# BpodFSM_2Plus_r1_2.net
KiCad netlist of a schematic drawn in EAGLE
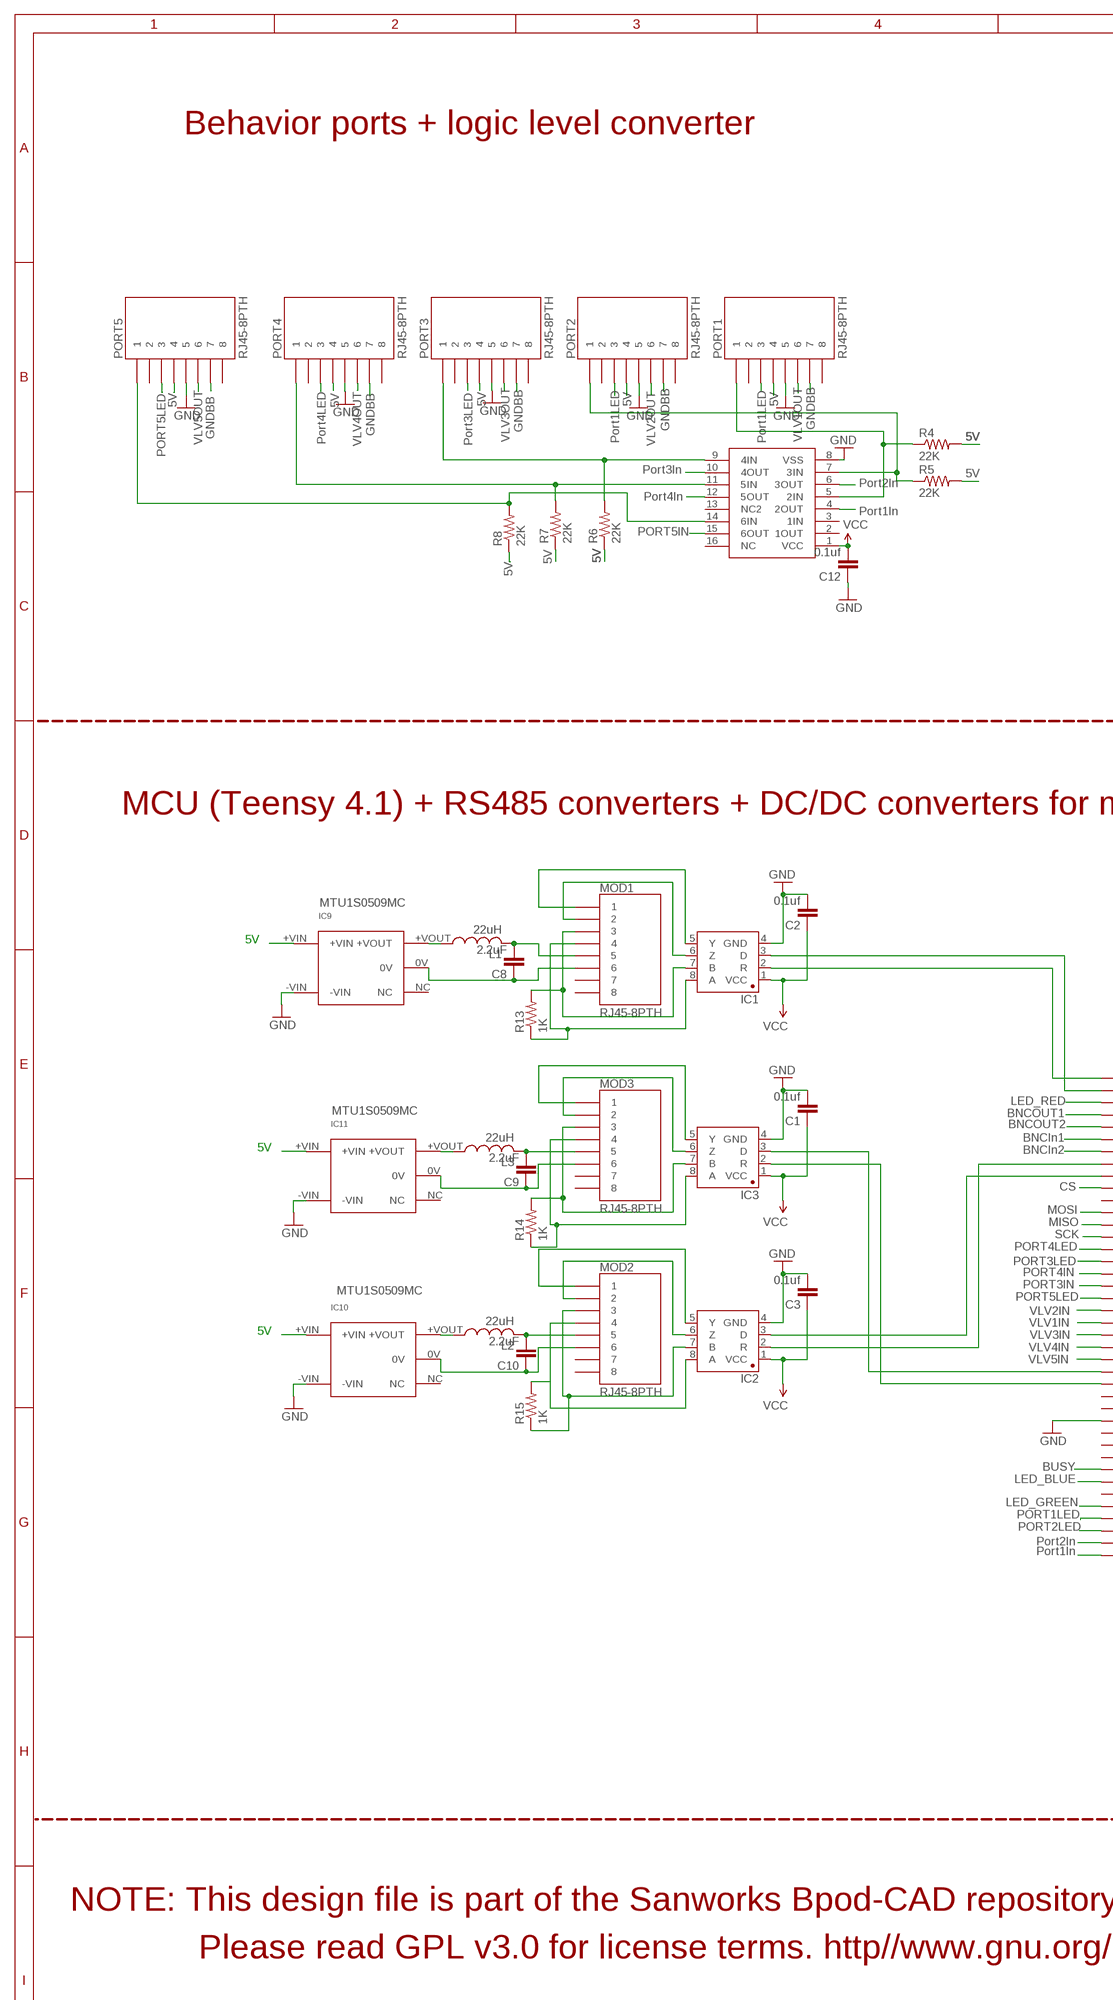
[diagram p0: schematic, sheet 1, part 1 of 2]
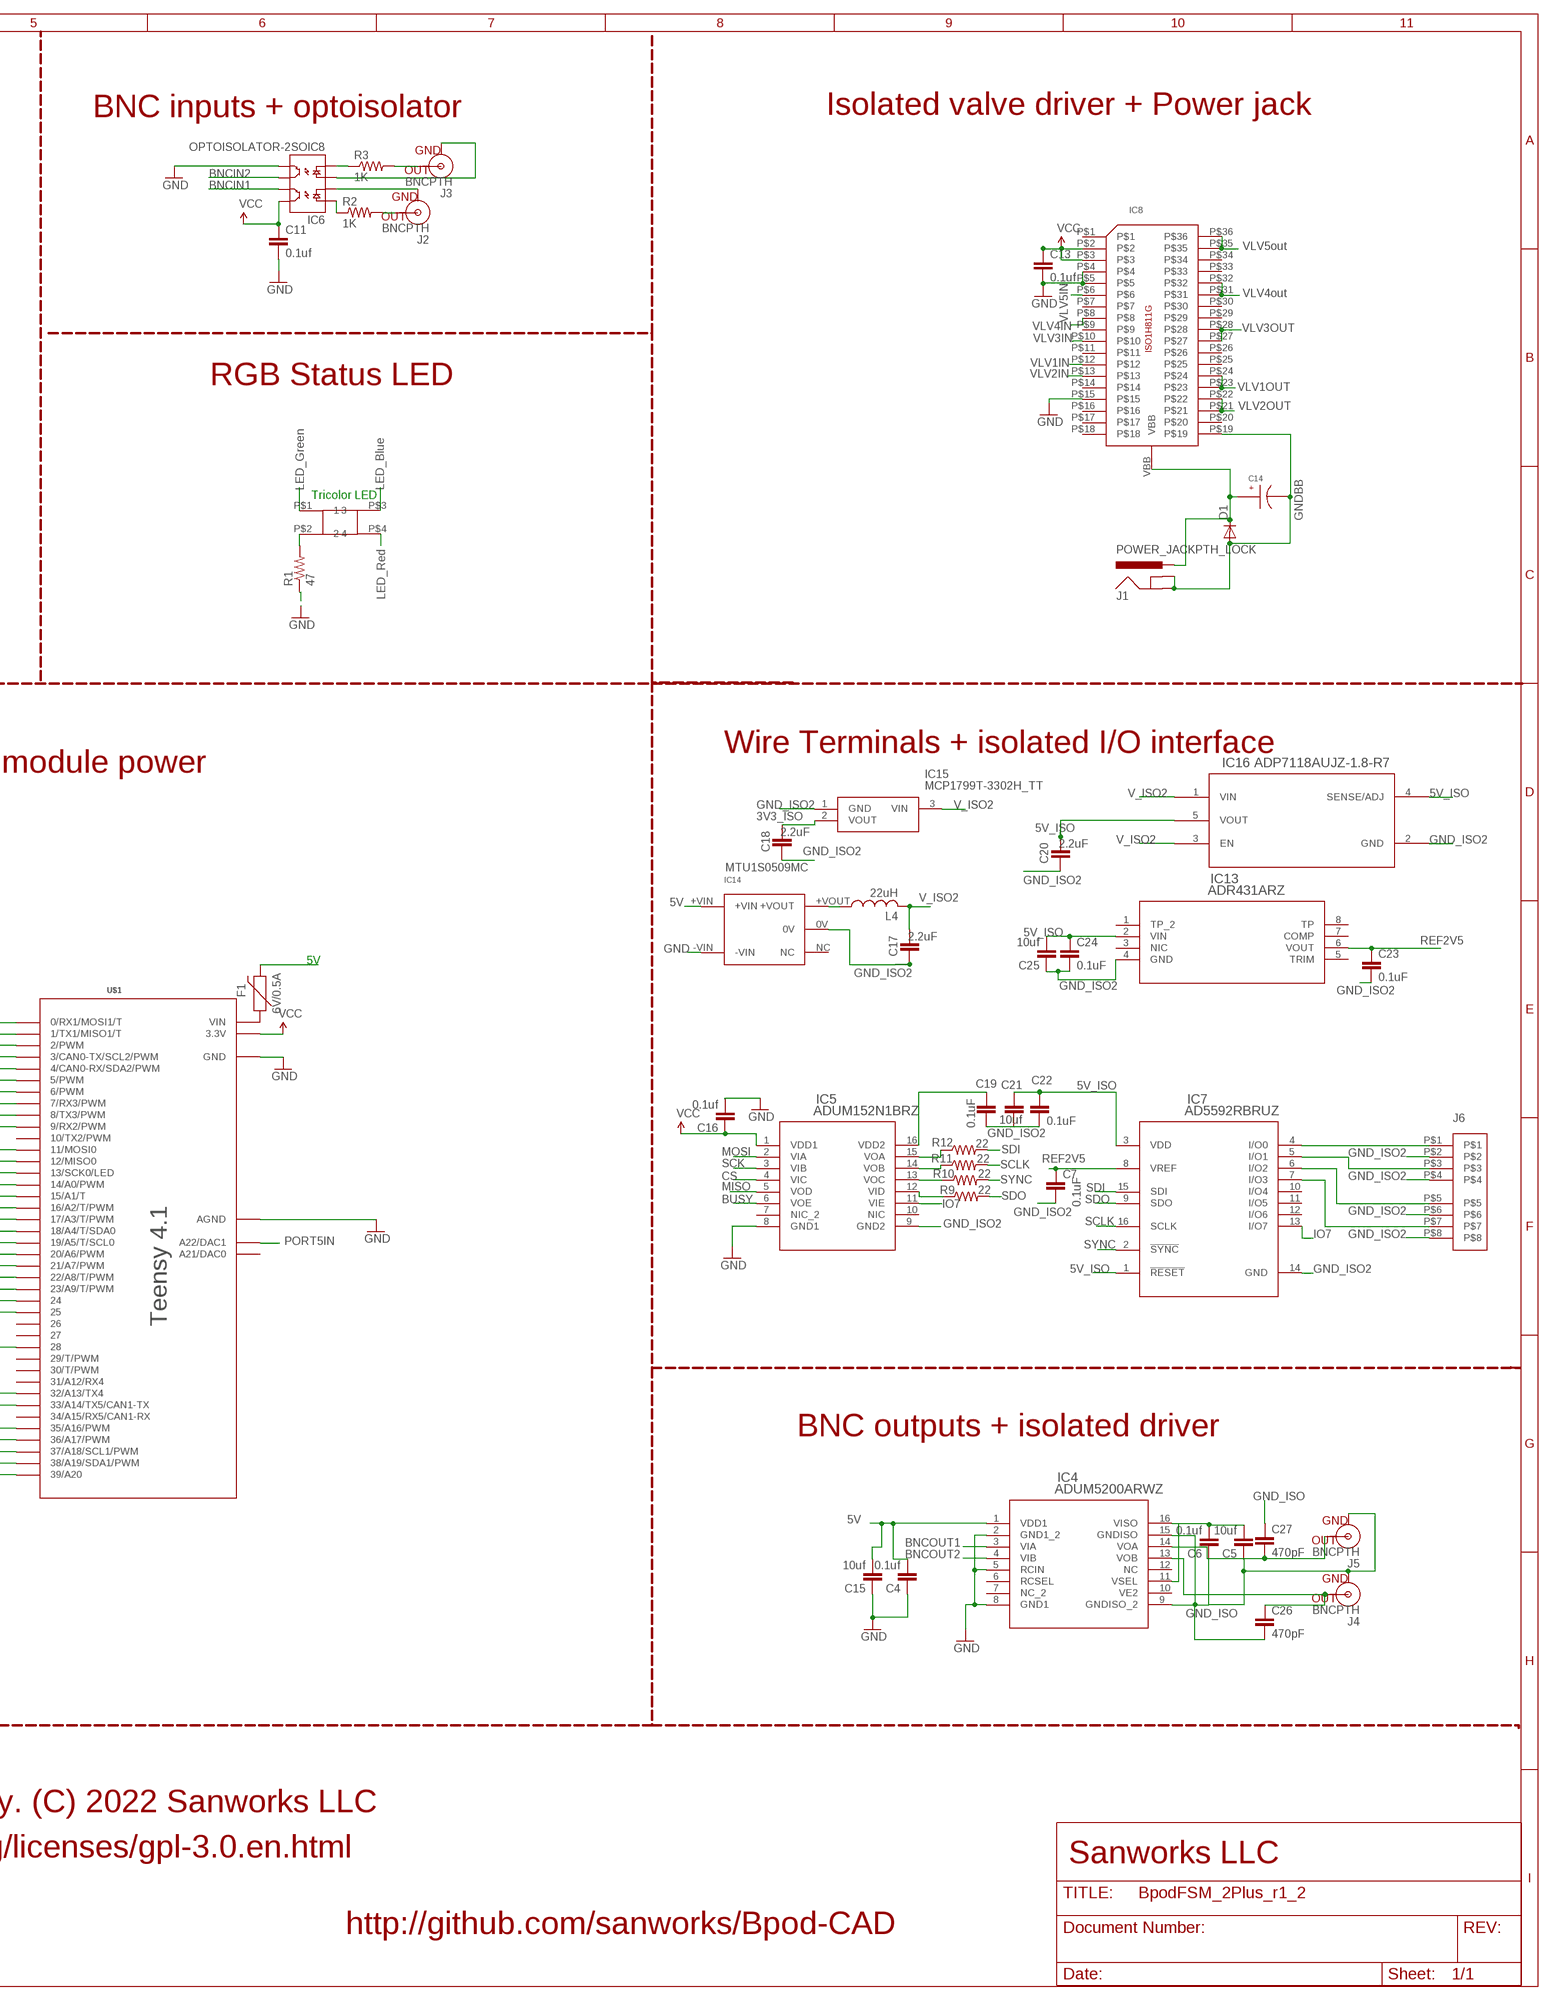
[diagram p1: schematic, sheet 1, part 2 of 2]

(export (version "E")
  (design (tool "Eeschema 10.0.6"))
  (components
    (comp (ref "C1")
      (value "0.1uf")
      (footprint "eagle-import:0805")
      (libsource (lib "eagle-import") (part "1.0UF-0805-25V-10%"))
    )
    (comp (ref "C2")
      (value "0.1uf")
      (footprint "eagle-import:0805")
      (libsource (lib "eagle-import") (part "1.0UF-0805-25V-10%"))
    )
    (comp (ref "C3")
      (value "0.1uf")
      (footprint "eagle-import:0805")
      (libsource (lib "eagle-import") (part "1.0UF-0805-25V-10%"))
    )
    (comp (ref "C4")
      (value "0.1uf")
      (footprint "eagle-import:0805")
      (libsource (lib "eagle-import") (part "1.0UF-0805-25V-10%"))
    )
    (comp (ref "C5")
      (value "10uf")
      (footprint "eagle-import:1206@1")
      (libsource (lib "eagle-import") (part "CAP1206"))
    )
    (comp (ref "C6")
      (value "0.1uf")
      (footprint "eagle-import:0805")
      (libsource (lib "eagle-import") (part "1.0UF-0805-25V-10%"))
    )
    (comp (ref "C7")
      (value "0.1uF")
      (footprint "eagle-import:0805")
      (libsource (lib "eagle-import") (part "1.0UF-0805-25V-10%"))
    )
    (comp (ref "C8")
      (value "2.2uF")
      (footprint "eagle-import:0805")
      (libsource (lib "eagle-import") (part "1.0UF-0805-25V-(+80/-20%)"))
    )
    (comp (ref "C9")
      (value "2.2uF")
      (footprint "eagle-import:0805")
      (libsource (lib "eagle-import") (part "1.0UF-0805-25V-(+80/-20%)"))
    )
    (comp (ref "C10")
      (value "2.2uF")
      (footprint "eagle-import:0805")
      (libsource (lib "eagle-import") (part "1.0UF-0805-25V-(+80/-20%)"))
    )
    (comp (ref "C11")
      (value "0.1uf")
      (footprint "eagle-import:0805")
      (libsource (lib "eagle-import") (part "1.0UF-0805-25V-10%"))
    )
    (comp (ref "C12")
      (value "0.1uf")
      (footprint "eagle-import:0805")
      (libsource (lib "eagle-import") (part "1.0UF-0805-25V-10%"))
    )
    (comp (ref "C13")
      (value "0.1uf")
      (footprint "eagle-import:0805")
      (libsource (lib "eagle-import") (part "1.0UF-0805-25V-10%"))
    )
    (comp (ref "C14")
      (value "EEE-FK1H100UR")
      (footprint "eagle-import:EEE-FK1H100UR")
      (libsource (lib "eagle-import") (part "EEE-FK1H100UR"))
    )
    (comp (ref "C15")
      (value "10uf")
      (footprint "eagle-import:1206@1")
      (libsource (lib "eagle-import") (part "CAP1206"))
    )
    (comp (ref "C16")
      (value "0.1uf")
      (footprint "eagle-import:0805")
      (libsource (lib "eagle-import") (part "1.0UF-0805-25V-10%"))
    )
    (comp (ref "C17")
      (value "2.2uF")
      (footprint "eagle-import:0805")
      (libsource (lib "eagle-import") (part "1.0UF-0805-25V-(+80/-20%)"))
    )
    (comp (ref "C18")
      (value "2.2uF")
      (footprint "eagle-import:0805")
      (libsource (lib "eagle-import") (part "1.0UF-0805-25V-(+80/-20%)"))
    )
    (comp (ref "C19")
      (value "0.1uF")
      (footprint "eagle-import:0805")
      (libsource (lib "eagle-import") (part "1.0UF-0805-25V-10%"))
    )
    (comp (ref "C20")
      (value "2.2uF")
      (footprint "eagle-import:0805")
      (libsource (lib "eagle-import") (part "1.0UF-0805-25V-(+80/-20%)"))
    )
    (comp (ref "C21")
      (value "10uf")
      (footprint "eagle-import:1206@1")
      (libsource (lib "eagle-import") (part "CAP1206"))
    )
    (comp (ref "C22")
      (value "0.1uF")
      (footprint "eagle-import:0805")
      (libsource (lib "eagle-import") (part "1.0UF-0805-25V-10%"))
    )
    (comp (ref "C23")
      (value "0.1uF")
      (footprint "eagle-import:0805")
      (libsource (lib "eagle-import") (part "1.0UF-0805-25V-10%"))
    )
    (comp (ref "C24")
      (value "0.1uF")
      (footprint "eagle-import:0805")
      (libsource (lib "eagle-import") (part "1.0UF-0805-25V-10%"))
    )
    (comp (ref "C25")
      (value "10uf")
      (footprint "eagle-import:1206@1")
      (libsource (lib "eagle-import") (part "CAP1206"))
    )
    (comp (ref "C26")
      (value "470pF")
      (footprint "eagle-import:0805")
      (libsource (lib "eagle-import") (part "1.0UF-0805-25V-10%"))
    )
    (comp (ref "C27")
      (value "470pF")
      (footprint "eagle-import:0805")
      (libsource (lib "eagle-import") (part "1.0UF-0805-25V-10%"))
    )
    (comp (ref "D1")
      (value "DIODE-DO214AA")
      (footprint "eagle-import:DO214AA")
      (libsource (lib "eagle-import") (part "DIODE-DO214AA"))
    )
    (comp (ref "F1")
      (value "6V/0.5A")
      (footprint "eagle-import:1206")
      (libsource (lib "eagle-import") (part "PPTC_HALF-AMP"))
    )
    (comp (ref "IC1")
      (value "SN65HVD31DR")
      (footprint "eagle-import:SO08")
      (libsource (lib "eagle-import") (part "SN65HVD31DR"))
    )
    (comp (ref "IC2")
      (value "SN65HVD31DR")
      (footprint "eagle-import:SO08")
      (libsource (lib "eagle-import") (part "SN65HVD31DR"))
    )
    (comp (ref "IC3")
      (value "SN65HVD31DR")
      (footprint "eagle-import:SO08")
      (libsource (lib "eagle-import") (part "SN65HVD31DR"))
    )
    (comp (ref "IC4")
      (value "ADUM5200ARWZ")
      (footprint "eagle-import:RW_16")
      (libsource (lib "eagle-import") (part "ADUM5200ARWZ"))
    )
    (comp (ref "IC5")
      (value "ADUM152N1BRZ")
      (footprint "eagle-import:R-16_ADI")
      (fields (field (name "COPYRIGHT") "Copyright (C) 2018 Accelerated Designs. All rights reserved"))
      (libsource (lib "eagle-import") (part "ADUM152N1BRZ"))
    )
    (comp (ref "IC6")
      (value "OPTOISOLATOR-2SOIC8")
      (footprint "eagle-import:SO08-2")
      (libsource (lib "eagle-import") (part "OPTOISOLATOR-2SOIC8"))
    )
    (comp (ref "IC7")
      (value "AD5592RBRUZ")
      (footprint "eagle-import:RU_16_ADI")
      (libsource (lib "eagle-import") (part "AD5592RBRUZ"))
    )
    (comp (ref "IC8")
      (value "ISO1H811G")
      (footprint "eagle-import:ISO1H811G")
      (libsource (lib "eagle-import") (part "ISO1H811G"))
    )
    (comp (ref "IC9")
      (value "9V")
      (footprint "eagle-import:MTU1D0505MC")
      (libsource (lib "eagle-import") (part "MTU1D0505MC"))
    )
    (comp (ref "IC10")
      (value "9V")
      (footprint "eagle-import:MTU1D0505MC")
      (libsource (lib "eagle-import") (part "MTU1D0505MC"))
    )
    (comp (ref "IC11")
      (value "9V")
      (footprint "eagle-import:MTU1D0505MC")
      (libsource (lib "eagle-import") (part "MTU1D0505MC"))
    )
    (comp (ref "IC12")
      (value "CD4050")
      (footprint "eagle-import:SO16")
      (libsource (lib "eagle-import") (part "CD4050"))
    )
    (comp (ref "IC13")
      (value "ADR431ARZ")
      (footprint "eagle-import:R_8_ADI")
      (libsource (lib "eagle-import") (part "ADR431ARZ"))
    )
    (comp (ref "IC14")
      (value "5V")
      (footprint "eagle-import:MTU1D0505MC")
      (libsource (lib "eagle-import") (part "MTU1D0505MC"))
    )
    (comp (ref "IC15")
      (value "MCP1799T-3302H_TT")
      (footprint "eagle-import:SOT95P237X112-3N")
      (fields
        (field (name "MANUFACTURER_PART_NUMBER") "MCP1799T-3302H/TT")
        (field (name "MOUSER_PART_NUMBER") "579-CP1799T-3302H/TT")
      )
      (libsource (lib "eagle-import") (part "MCP1799T-3302H_TT"))
    )
    (comp (ref "IC16")
      (value "ADP7118AUJZ-1.8-R7")
      (footprint "eagle-import:UJ_5")
      (libsource (lib "eagle-import") (part "ADP7118AUJZ-1.8-R7"))
    )
    (comp (ref "J1")
      (value "POWER_JACKPTH_LOCK")
      (footprint "eagle-import:POWER_JACK_PTH_LOCK")
      (libsource (lib "eagle-import") (part "POWER_JACKPTH_LOCK"))
    )
    (comp (ref "J2")
      (value "BNCPTH")
      (footprint "eagle-import:BNC")
      (libsource (lib "eagle-import") (part "BNCPTH"))
    )
    (comp (ref "J3")
      (value "BNCPTH")
      (footprint "eagle-import:BNC")
      (libsource (lib "eagle-import") (part "BNCPTH"))
    )
    (comp (ref "J4")
      (value "BNCPTH")
      (footprint "eagle-import:BNC")
      (libsource (lib "eagle-import") (part "BNCPTH"))
    )
    (comp (ref "J5")
      (value "BNCPTH")
      (footprint "eagle-import:BNC")
      (libsource (lib "eagle-import") (part "BNCPTH"))
    )
    (comp (ref "J6")
      (value "8POS_MOLEX_SOCKET")
      (footprint "eagle-import:8POS_MOLEX_SOCKET")
      (libsource (lib "eagle-import") (part "8POS_MOLEX_SOCKET"))
    )
    (comp (ref "L1")
      (value "22uH")
      (footprint "eagle-import:L3225M")
      (libsource (lib "eagle-import") (part "L-USL3225M"))
    )
    (comp (ref "L2")
      (value "22uH")
      (footprint "eagle-import:L3225M")
      (libsource (lib "eagle-import") (part "L-USL3225M"))
    )
    (comp (ref "L3")
      (value "22uH")
      (footprint "eagle-import:L3225M")
      (libsource (lib "eagle-import") (part "L-USL3225M"))
    )
    (comp (ref "L4")
      (value "22uH")
      (footprint "eagle-import:L3225M")
      (libsource (lib "eagle-import") (part "L-USL3225M"))
    )
    (comp (ref "MOD1")
      (value "RJ45-8PTH")
      (footprint "eagle-import:RJ45-8")
      (libsource (lib "eagle-import") (part "RJ45-8PTH"))
    )
    (comp (ref "MOD2")
      (value "RJ45-8PTH")
      (footprint "eagle-import:RJ45-8")
      (libsource (lib "eagle-import") (part "RJ45-8PTH"))
    )
    (comp (ref "MOD3")
      (value "RJ45-8PTH")
      (footprint "eagle-import:RJ45-8")
      (libsource (lib "eagle-import") (part "RJ45-8PTH"))
    )
    (comp (ref "PORT1")
      (value "RJ45-8PTH")
      (footprint "eagle-import:RJ45-8")
      (libsource (lib "eagle-import") (part "RJ45-8PTH"))
    )
    (comp (ref "PORT2")
      (value "RJ45-8PTH")
      (footprint "eagle-import:RJ45-8")
      (libsource (lib "eagle-import") (part "RJ45-8PTH"))
    )
    (comp (ref "PORT3")
      (value "RJ45-8PTH")
      (footprint "eagle-import:RJ45-8")
      (libsource (lib "eagle-import") (part "RJ45-8PTH"))
    )
    (comp (ref "PORT4")
      (value "RJ45-8PTH")
      (footprint "eagle-import:RJ45-8")
      (libsource (lib "eagle-import") (part "RJ45-8PTH"))
    )
    (comp (ref "PORT5")
      (value "RJ45-8PTH")
      (footprint "eagle-import:RJ45-8")
      (libsource (lib "eagle-import") (part "RJ45-8PTH"))
    )
    (comp (ref "R1")
      (value "47")
      (footprint "eagle-import:1206")
      (libsource (lib "eagle-import") (part "RESISTOR1206"))
    )
    (comp (ref "R2")
      (value "1K")
      (footprint "eagle-import:1206")
      (libsource (lib "eagle-import") (part "SparkFun-Resistors_RESISTOR1206"))
    )
    (comp (ref "R3")
      (value "1K")
      (footprint "eagle-import:1206")
      (libsource (lib "eagle-import") (part "SparkFun-Resistors_RESISTOR1206"))
    )
    (comp (ref "R4")
      (value "22K")
      (footprint "eagle-import:1206")
      (libsource (lib "eagle-import") (part "SparkFun-Resistors_RESISTOR1206"))
    )
    (comp (ref "R5")
      (value "22K")
      (footprint "eagle-import:1206")
      (libsource (lib "eagle-import") (part "SparkFun-Resistors_RESISTOR1206"))
    )
    (comp (ref "R6")
      (value "22K")
      (footprint "eagle-import:1206")
      (libsource (lib "eagle-import") (part "SparkFun-Resistors_RESISTOR1206"))
    )
    (comp (ref "R7")
      (value "22K")
      (footprint "eagle-import:1206")
      (libsource (lib "eagle-import") (part "SparkFun-Resistors_RESISTOR1206"))
    )
    (comp (ref "R8")
      (value "22K")
      (footprint "eagle-import:1206")
      (libsource (lib "eagle-import") (part "SparkFun-Resistors_RESISTOR1206"))
    )
    (comp (ref "R9")
      (value "22")
      (footprint "eagle-import:R0805")
      (libsource (lib "eagle-import") (part "R-US_R0805"))
    )
    (comp (ref "R10")
      (value "22")
      (footprint "eagle-import:R0805")
      (libsource (lib "eagle-import") (part "R-US_R0805"))
    )
    (comp (ref "R11")
      (value "22")
      (footprint "eagle-import:R0805")
      (libsource (lib "eagle-import") (part "R-US_R0805"))
    )
    (comp (ref "R12")
      (value "22")
      (footprint "eagle-import:R0805")
      (libsource (lib "eagle-import") (part "R-US_R0805"))
    )
    (comp (ref "R13")
      (value "1K")
      (footprint "eagle-import:1206")
      (libsource (lib "eagle-import") (part "SparkFun-Resistors_RESISTOR1206"))
    )
    (comp (ref "R14")
      (value "1K")
      (footprint "eagle-import:1206")
      (libsource (lib "eagle-import") (part "SparkFun-Resistors_RESISTOR1206"))
    )
    (comp (ref "R15")
      (value "1K")
      (footprint "eagle-import:1206")
      (libsource (lib "eagle-import") (part "SparkFun-Resistors_RESISTOR1206"))
    )
    (comp (ref "U$1")
      (value "TEENSY_3.6_DIL")
      (footprint "eagle-import:TEENSY_3.6_DIL")
      (libsource (lib "eagle-import") (part "TEENSY_3.6_DIL"))
    )
    (comp (ref "U$8")
      (value "SQUARE_TRICOLOR_LED")
      (footprint "eagle-import:SQUARE_TRICOLOR_LED")
      (libsource (lib "eagle-import") (part "SQUARE_TRICOLOR_LED"))
    )
  )
  (nets
    (net (code "1") (name "/3V3_ISO") (class "Default")
      (node (ref "C18") (pin "2") (pinfunction "2_2") (pintype "passive"))
      (node (ref "C19") (pin "1") (pinfunction "1_1") (pintype "passive"))
      (node (ref "IC15") (pin "2") (pinfunction "VOUT_2") (pintype "bidirectional"))
      (node (ref "IC5") (pin "16") (pinfunction "VDD2_16") (pintype "power_in"))
    )
    (net (code "2") (name "/5V") (class "Default")
      (node (ref "C15") (pin "2") (pinfunction "2_2") (pintype "passive"))
      (node (ref "C4") (pin "2") (pinfunction "2_2") (pintype "passive"))
      (node (ref "F1") (pin "2") (pinfunction "2_2") (pintype "bidirectional"))
      (node (ref "IC10") (pin "+VIN") (pinfunction "+VIN_+VIN") (pintype "bidirectional"))
      (node (ref "IC11") (pin "+VIN") (pinfunction "+VIN_+VIN") (pintype "bidirectional"))
      (node (ref "IC14") (pin "+VIN") (pinfunction "+VIN_+VIN") (pintype "bidirectional"))
      (node (ref "IC4") (pin "1") (pinfunction "VDD1_1") (pintype "passive"))
      (node (ref "IC9") (pin "+VIN") (pinfunction "+VIN_+VIN") (pintype "bidirectional"))
      (node (ref "PORT1") (pin "4") (pinfunction "4_4") (pintype "bidirectional"))
      (node (ref "PORT2") (pin "4") (pinfunction "4_4") (pintype "bidirectional"))
      (node (ref "PORT3") (pin "4") (pinfunction "4_4") (pintype "bidirectional"))
      (node (ref "PORT4") (pin "4") (pinfunction "4_4") (pintype "bidirectional"))
      (node (ref "PORT5") (pin "4") (pinfunction "4_4") (pintype "bidirectional"))
      (node (ref "R4") (pin "2") (pinfunction "2_2") (pintype "passive"))
      (node (ref "R5") (pin "2") (pinfunction "2_2") (pintype "passive"))
      (node (ref "R6") (pin "1") (pinfunction "1_1") (pintype "passive"))
      (node (ref "R7") (pin "1") (pinfunction "1_1") (pintype "passive"))
      (node (ref "R8") (pin "1") (pinfunction "1_1") (pintype "passive"))
    )
    (net (code "3") (name "/5V_ISO") (class "Default")
      (node (ref "C20") (pin "2") (pinfunction "2_2") (pintype "passive"))
      (node (ref "C21") (pin "2") (pinfunction "2_2") (pintype "passive"))
      (node (ref "C22") (pin "1") (pinfunction "1_1") (pintype "passive"))
      (node (ref "C24") (pin "1") (pinfunction "1_1") (pintype "passive"))
      (node (ref "C25") (pin "2") (pinfunction "2_2") (pintype "passive"))
      (node (ref "IC13") (pin "2") (pinfunction "VIN_2") (pintype "input"))
      (node (ref "IC16") (pin "4") (pinfunction "SENSE/ADJ_4") (pintype "passive"))
      (node (ref "IC16") (pin "5") (pinfunction "VOUT_5") (pintype "passive"))
      (node (ref "IC7") (pin "1") (pinfunction "~{RESET}_1") (pintype "passive"))
      (node (ref "IC7") (pin "3") (pinfunction "VDD_3") (pintype "passive"))
    )
    (net (code "4") (name "/BNCIN1") (class "Default")
      (node (ref "IC6") (pin "7") (pinfunction "EM1_7") (pintype "bidirectional"))
      (node (ref "U$1") (pin "6") (pinfunction "6/PWM_6") (pintype "bidirectional"))
    )
    (net (code "5") (name "/BNCIN2") (class "Default")
      (node (ref "IC6") (pin "6") (pinfunction "CL2_6") (pintype "bidirectional"))
      (node (ref "U$1") (pin "5") (pinfunction "5/PWM_5") (pintype "bidirectional"))
    )
    (net (code "6") (name "/BNCOUT1") (class "Default")
      (node (ref "IC4") (pin "3") (pinfunction "VIA_3") (pintype "passive"))
      (node (ref "U$1") (pin "3") (pinfunction "3/CAN0-TX/SCL2/PWM_3") (pintype "bidirectional"))
    )
    (net (code "7") (name "/BNCOUT2") (class "Default")
      (node (ref "IC4") (pin "4") (pinfunction "VIB_4") (pintype "passive"))
      (node (ref "U$1") (pin "4") (pinfunction "4/CAN0-RX/SDA2/PWM_4") (pintype "bidirectional"))
    )
    (net (code "8") (name "/BUSY") (class "Default")
      (node (ref "IC5") (pin "6") (pinfunction "VOE_6") (pintype "output"))
      (node (ref "U$1") (pin "32/A13") (pinfunction "32/A13/TX4_32/A13") (pintype "bidirectional"))
    )
    (net (code "9") (name "/CS") (class "Default")
      (node (ref "IC5") (pin "4") (pinfunction "VIC_4") (pintype "input"))
      (node (ref "U$1") (pin "9") (pinfunction "9/RX2/PWM_9") (pintype "bidirectional"))
    )
    (net (code "10") (name "/GNDBB") (class "Default")
      (node (ref "C14") (pin "CATHODE") (pinfunction "CATHODE_CATHODE") (pintype "bidirectional"))
      (node (ref "D1") (pin "A") (pinfunction "A_A") (pintype "passive"))
      (node (ref "IC8") (pin "P$19") (pinfunction "P$19_P$19") (pintype "bidirectional"))
      (node (ref "J1") (pin "GND") (pinfunction "GND_GND") (pintype "bidirectional"))
      (node (ref "J1") (pin "GNDBREAK") (pinfunction "GNDBREAK_GNDBREAK") (pintype "bidirectional"))
      (node (ref "PORT1") (pin "7") (pinfunction "7_7") (pintype "bidirectional"))
      (node (ref "PORT2") (pin "7") (pinfunction "7_7") (pintype "bidirectional"))
      (node (ref "PORT3") (pin "7") (pinfunction "7_7") (pintype "bidirectional"))
      (node (ref "PORT4") (pin "7") (pinfunction "7_7") (pintype "bidirectional"))
      (node (ref "PORT5") (pin "7") (pinfunction "7_7") (pintype "bidirectional"))
    )
    (net (code "11") (name "/GND_ISO") (class "Default")
      (node (ref "C26") (pin "2") (pinfunction "2_2") (pintype "passive"))
      (node (ref "C27") (pin "1") (pinfunction "1_1") (pintype "passive"))
      (node (ref "C5") (pin "1") (pinfunction "1_1") (pintype "passive"))
      (node (ref "C6") (pin "1") (pinfunction "1_1") (pintype "passive"))
      (node (ref "IC4") (pin "15") (pinfunction "GNDISO_15") (pintype "passive"))
      (node (ref "IC4") (pin "9") (pinfunction "GNDISO_2_9") (pintype "passive"))
      (node (ref "J4") (pin "GND") (pinfunction "GND_GND") (pintype "bidirectional"))
      (node (ref "J5") (pin "GND") (pinfunction "GND_GND") (pintype "bidirectional"))
    )
    (net (code "12") (name "/GND_ISO2") (class "Default")
      (node (ref "C17") (pin "1") (pinfunction "1_1") (pintype "passive"))
      (node (ref "C18") (pin "1") (pinfunction "1_1") (pintype "passive"))
      (node (ref "C19") (pin "2") (pinfunction "2_2") (pintype "passive"))
      (node (ref "C20") (pin "1") (pinfunction "1_1") (pintype "passive"))
      (node (ref "C21") (pin "1") (pinfunction "1_1") (pintype "passive"))
      (node (ref "C22") (pin "2") (pinfunction "2_2") (pintype "passive"))
      (node (ref "C23") (pin "2") (pinfunction "2_2") (pintype "passive"))
      (node (ref "C24") (pin "2") (pinfunction "2_2") (pintype "passive"))
      (node (ref "C25") (pin "1") (pinfunction "1_1") (pintype "passive"))
      (node (ref "C7") (pin "2") (pinfunction "2_2") (pintype "passive"))
      (node (ref "IC13") (pin "4") (pinfunction "GND_4") (pintype "power_in"))
      (node (ref "IC14") (pin "0V") (pinfunction "0V_0V") (pintype "bidirectional"))
      (node (ref "IC15") (pin "1") (pinfunction "GND_1") (pintype "bidirectional"))
      (node (ref "IC16") (pin "2") (pinfunction "GND_2") (pintype "passive"))
      (node (ref "IC5") (pin "9") (pinfunction "GND2_9") (pintype "passive"))
      (node (ref "IC7") (pin "14") (pinfunction "GND_14") (pintype "passive"))
      (node (ref "J6") (pin "P$2") (pinfunction "P$2_P$2") (pintype "bidirectional"))
      (node (ref "J6") (pin "P$4") (pinfunction "P$4_P$4") (pintype "bidirectional"))
      (node (ref "J6") (pin "P$6") (pinfunction "P$6_P$6") (pintype "bidirectional"))
      (node (ref "J6") (pin "P$8") (pinfunction "P$8_P$8") (pintype "bidirectional"))
    )
    (net (code "13") (name "/IO7") (class "Default")
      (node (ref "IC5") (pin "11") (pinfunction "VIE_11") (pintype "input"))
      (node (ref "IC7") (pin "13") (pinfunction "I/O7_13") (pintype "passive"))
    )
    (net (code "14") (name "/LED_BLUE") (class "Default")
      (node (ref "U$1") (pin "33/A14") (pinfunction "33/A14/TX5/CAN1-TX_33/A14") (pintype "bidirectional"))
      (node (ref "U$8") (pin "P$3") (pinfunction "3_P$3") (pintype "bidirectional"))
    )
    (net (code "15") (name "/LED_GREEN") (class "Default")
      (node (ref "U$1") (pin "35/A16") (pinfunction "35/A16/PWM_35/A16") (pintype "bidirectional"))
      (node (ref "U$8") (pin "P$1") (pinfunction "1_P$1") (pintype "bidirectional"))
    )
    (net (code "16") (name "/LED_RED") (class "Default")
      (node (ref "U$1") (pin "2") (pinfunction "2/PWM_2") (pintype "bidirectional"))
      (node (ref "U$8") (pin "P$4") (pinfunction "4_P$4") (pintype "bidirectional"))
    )
    (net (code "17") (name "/MISO") (class "Default")
      (node (ref "IC5") (pin "5") (pinfunction "VOD_5") (pintype "output"))
      (node (ref "U$1") (pin "12") (pinfunction "12/MISO0_12") (pintype "bidirectional"))
    )
    (net (code "18") (name "/MOSI") (class "Default")
      (node (ref "IC5") (pin "2") (pinfunction "VIA_2") (pintype "input"))
      (node (ref "U$1") (pin "11") (pinfunction "11/MOSI0_11") (pintype "bidirectional"))
    )
    (net (code "19") (name "/PORT1IN") (class "Default")
      (node (ref "IC12") (pin "4") (pinfunction "2OUT_4") (pintype "bidirectional"))
      (node (ref "U$1") (pin "39/A20") (pinfunction "39/A20_39/A20") (pintype "bidirectional"))
    )
    (net (code "20") (name "/PORT1LED") (class "Default")
      (node (ref "PORT1") (pin "3") (pinfunction "3_3") (pintype "bidirectional"))
      (node (ref "U$1") (pin "36/A17") (pinfunction "36/A17/PWM_36/A17") (pintype "bidirectional"))
    )
    (net (code "21") (name "/PORT2IN") (class "Default")
      (node (ref "IC12") (pin "6") (pinfunction "3OUT_6") (pintype "bidirectional"))
      (node (ref "U$1") (pin "38/A19") (pinfunction "38/A19/SDA1/PWM_38/A19") (pintype "bidirectional"))
    )
    (net (code "22") (name "/PORT2LED") (class "Default")
      (node (ref "PORT2") (pin "3") (pinfunction "3_3") (pintype "bidirectional"))
      (node (ref "U$1") (pin "37/A18") (pinfunction "37/A18/SCL1/PWM_37/A18") (pintype "bidirectional"))
    )
    (net (code "23") (name "/PORT3IN") (class "Default")
      (node (ref "IC12") (pin "10") (pinfunction "4OUT_10") (pintype "bidirectional"))
      (node (ref "U$1") (pin "17/A3") (pinfunction "17/A3/T/PWM_17/A3") (pintype "bidirectional"))
    )
    (net (code "24") (name "/PORT3LED") (class "Default")
      (node (ref "PORT3") (pin "3") (pinfunction "3_3") (pintype "bidirectional"))
      (node (ref "U$1") (pin "15/A1") (pinfunction "15/A1/T_15/A1") (pintype "bidirectional"))
    )
    (net (code "25") (name "/PORT4IN") (class "Default")
      (node (ref "IC12") (pin "12") (pinfunction "5OUT_12") (pintype "bidirectional"))
      (node (ref "U$1") (pin "16/A2") (pinfunction "16/A2/T/PWM_16/A2") (pintype "bidirectional"))
    )
    (net (code "26") (name "/PORT4LED") (class "Default")
      (node (ref "PORT4") (pin "3") (pinfunction "3_3") (pintype "bidirectional"))
      (node (ref "U$1") (pin "14/A0") (pinfunction "14/A0/PWM_14/A0") (pintype "bidirectional"))
    )
    (net (code "27") (name "/PORT5IN") (class "Default")
      (node (ref "IC12") (pin "15") (pinfunction "6OUT_15") (pintype "bidirectional"))
      (node (ref "U$1") (pin "A22") (pinfunction "A22/DAC1_A22") (pintype "bidirectional"))
    )
    (net (code "28") (name "/PORT5LED") (class "Default")
      (node (ref "PORT5") (pin "3") (pinfunction "3_3") (pintype "bidirectional"))
      (node (ref "U$1") (pin "18/A4") (pinfunction "18/A4/T/SDA0_18/A4") (pintype "bidirectional"))
    )
    (net (code "29") (name "/REF2V5") (class "Default")
      (node (ref "C23") (pin "1") (pinfunction "1_1") (pintype "passive"))
      (node (ref "C7") (pin "1") (pinfunction "1_1") (pintype "passive"))
      (node (ref "IC13") (pin "6") (pinfunction "VOUT_6") (pintype "output"))
      (node (ref "IC7") (pin "8") (pinfunction "VREF_8") (pintype "passive"))
    )
    (net (code "30") (name "/SCK") (class "Default")
      (node (ref "IC5") (pin "3") (pinfunction "VIB_3") (pintype "input"))
      (node (ref "U$1") (pin "13") (pinfunction "13/SCK0/LED_13") (pintype "bidirectional"))
    )
    (net (code "31") (name "/SCLK") (class "Default")
      (node (ref "IC7") (pin "16") (pinfunction "SCLK_16") (pintype "passive"))
      (node (ref "R11") (pin "2") (pinfunction "2_2") (pintype "passive"))
    )
    (net (code "32") (name "/SDI") (class "Default")
      (node (ref "IC7") (pin "15") (pinfunction "SDI_15") (pintype "passive"))
      (node (ref "R12") (pin "2") (pinfunction "2_2") (pintype "passive"))
    )
    (net (code "33") (name "/SDO") (class "Default")
      (node (ref "IC7") (pin "9") (pinfunction "SDO_9") (pintype "passive"))
      (node (ref "R9") (pin "2") (pinfunction "2_2") (pintype "passive"))
    )
    (net (code "34") (name "/SYNC") (class "Default")
      (node (ref "IC7") (pin "2") (pinfunction "~{SYNC}_2") (pintype "passive"))
      (node (ref "R10") (pin "2") (pinfunction "2_2") (pintype "passive"))
    )
    (net (code "35") (name "/VLV1IN") (class "Default")
      (node (ref "IC8") (pin "P$12") (pinfunction "P$12_P$12") (pintype "bidirectional"))
      (node (ref "U$1") (pin "20/A6") (pinfunction "20/A6/PWM_20/A6") (pintype "bidirectional"))
    )
    (net (code "36") (name "/VLV1OUT") (class "Default")
      (node (ref "IC8") (pin "P$23") (pinfunction "P$23_P$23") (pintype "bidirectional"))
      (node (ref "IC8") (pin "P$24") (pinfunction "P$24_P$24") (pintype "bidirectional"))
      (node (ref "PORT1") (pin "6") (pinfunction "6_6") (pintype "bidirectional"))
    )
    (net (code "37") (name "/VLV2IN") (class "Default")
      (node (ref "IC8") (pin "P$13") (pinfunction "P$13_P$13") (pintype "bidirectional"))
      (node (ref "U$1") (pin "19/A5") (pinfunction "19/A5/T/SCL0_19/A5") (pintype "bidirectional"))
    )
    (net (code "38") (name "/VLV2OUT") (class "Default")
      (node (ref "IC8") (pin "P$21") (pinfunction "P$21_P$21") (pintype "bidirectional"))
      (node (ref "IC8") (pin "P$22") (pinfunction "P$22_P$22") (pintype "bidirectional"))
      (node (ref "PORT2") (pin "6") (pinfunction "6_6") (pintype "bidirectional"))
    )
    (net (code "39") (name "/VLV3IN") (class "Default")
      (node (ref "IC8") (pin "P$10") (pinfunction "P$10_P$10") (pintype "bidirectional"))
      (node (ref "U$1") (pin "21/A7") (pinfunction "21/A7/PWM_21/A7") (pintype "bidirectional"))
    )
    (net (code "40") (name "/VLV3OUT") (class "Default")
      (node (ref "IC8") (pin "P$27") (pinfunction "P$27_P$27") (pintype "bidirectional"))
      (node (ref "IC8") (pin "P$28") (pinfunction "P$28_P$28") (pintype "bidirectional"))
      (node (ref "PORT3") (pin "6") (pinfunction "6_6") (pintype "bidirectional"))
    )
    (net (code "41") (name "/VLV4IN") (class "Default")
      (node (ref "IC8") (pin "P$8") (pinfunction "P$8_P$8") (pintype "bidirectional"))
      (node (ref "U$1") (pin "22/A8") (pinfunction "22/A8/T/PWM_22/A8") (pintype "bidirectional"))
    )
    (net (code "42") (name "/VLV4OUT") (class "Default")
      (node (ref "IC8") (pin "P$31") (pinfunction "P$31_P$31") (pintype "bidirectional"))
      (node (ref "IC8") (pin "P$32") (pinfunction "P$32_P$32") (pintype "bidirectional"))
      (node (ref "PORT4") (pin "6") (pinfunction "6_6") (pintype "bidirectional"))
    )
    (net (code "43") (name "/VLV5IN") (class "Default")
      (node (ref "IC8") (pin "P$6") (pinfunction "P$6_P$6") (pintype "bidirectional"))
      (node (ref "U$1") (pin "23/A9") (pinfunction "23/A9/T/PWM_23/A9") (pintype "bidirectional"))
    )
    (net (code "44") (name "/VLV5OUT") (class "Default")
      (node (ref "IC8") (pin "P$35") (pinfunction "P$35_P$35") (pintype "bidirectional"))
      (node (ref "IC8") (pin "P$36") (pinfunction "P$36_P$36") (pintype "bidirectional"))
      (node (ref "PORT5") (pin "6") (pinfunction "6_6") (pintype "bidirectional"))
    )
    (net (code "45") (name "/V_ISO2") (class "Default")
      (node (ref "C17") (pin "2") (pinfunction "2_2") (pintype "passive"))
      (node (ref "IC15") (pin "3") (pinfunction "VIN_3") (pintype "bidirectional"))
      (node (ref "IC16") (pin "1") (pinfunction "VIN_1") (pintype "passive"))
      (node (ref "IC16") (pin "3") (pinfunction "EN_3") (pintype "passive"))
      (node (ref "L4") (pin "2") (pinfunction "2_2") (pintype "passive"))
    )
    (net (code "46") (name "GND") (class "Default")
      (node (ref "C1") (pin "2") (pinfunction "2_2") (pintype "passive"))
      (node (ref "C11") (pin "2") (pinfunction "2_2") (pintype "passive"))
      (node (ref "C12") (pin "1") (pinfunction "1_1") (pintype "passive"))
      (node (ref "C13") (pin "2") (pinfunction "2_2") (pintype "passive"))
      (node (ref "C15") (pin "1") (pinfunction "1_1") (pintype "passive"))
      (node (ref "C16") (pin "2") (pinfunction "2_2") (pintype "passive"))
      (node (ref "C2") (pin "2") (pinfunction "2_2") (pintype "passive"))
      (node (ref "C3") (pin "2") (pinfunction "2_2") (pintype "passive"))
      (node (ref "C4") (pin "1") (pinfunction "1_1") (pintype "passive"))
      (node (ref "IC1") (pin "4") (pinfunction "GND_4") (pintype "bidirectional"))
      (node (ref "IC10") (pin "-VIN") (pinfunction "-VIN_-VIN") (pintype "bidirectional"))
      (node (ref "IC11") (pin "-VIN") (pinfunction "-VIN_-VIN") (pintype "bidirectional"))
      (node (ref "IC12") (pin "8") (pinfunction "VSS_8") (pintype "bidirectional"))
      (node (ref "IC14") (pin "-VIN") (pinfunction "-VIN_-VIN") (pintype "bidirectional"))
      (node (ref "IC2") (pin "4") (pinfunction "GND_4") (pintype "bidirectional"))
      (node (ref "IC3") (pin "4") (pinfunction "GND_4") (pintype "bidirectional"))
      (node (ref "IC4") (pin "2") (pinfunction "GND1_2_2") (pintype "passive"))
      (node (ref "IC4") (pin "5") (pinfunction "RCIN_5") (pintype "passive"))
      (node (ref "IC4") (pin "8") (pinfunction "GND1_8") (pintype "passive"))
      (node (ref "IC5") (pin "8") (pinfunction "GND1_8") (pintype "passive"))
      (node (ref "IC6") (pin "5") (pinfunction "EM2_5") (pintype "bidirectional"))
      (node (ref "IC8") (pin "P$15") (pinfunction "P$15_P$15") (pintype "bidirectional"))
      (node (ref "IC8") (pin "P$4") (pinfunction "P$4_P$4") (pintype "bidirectional"))
      (node (ref "IC8") (pin "P$5") (pinfunction "P$5_P$5") (pintype "bidirectional"))
      (node (ref "IC9") (pin "-VIN") (pinfunction "-VIN_-VIN") (pintype "bidirectional"))
      (node (ref "PORT1") (pin "5") (pinfunction "5_5") (pintype "bidirectional"))
      (node (ref "PORT2") (pin "5") (pinfunction "5_5") (pintype "bidirectional"))
      (node (ref "PORT3") (pin "5") (pinfunction "5_5") (pintype "bidirectional"))
      (node (ref "PORT4") (pin "5") (pinfunction "5_5") (pintype "bidirectional"))
      (node (ref "PORT5") (pin "5") (pinfunction "5_5") (pintype "bidirectional"))
      (node (ref "R1") (pin "1") (pinfunction "1_1") (pintype "passive"))
      (node (ref "U$1") (pin "28") (pinfunction "28_28") (pintype "bidirectional"))
      (node (ref "U$1") (pin "AGND") (pinfunction "AGND_AGND") (pintype "power_in"))
      (node (ref "U$1") (pin "GND") (pinfunction "GND_GND") (pintype "power_in"))
      (node (ref "U$1") (pin "GND1") (pinfunction "GND_GND1") (pintype "power_in"))
    )
    (net (code "47") (name "Net-(C8-Pad1)") (class "Default")
      (node (ref "C8") (pin "1") (pinfunction "1_1") (pintype "passive"))
      (node (ref "IC9") (pin "0V") (pinfunction "0V_0V") (pintype "bidirectional"))
      (node (ref "MOD1") (pin "6") (pinfunction "6_6") (pintype "bidirectional"))
    )
    (net (code "48") (name "Net-(C8-Pad2)") (class "Default")
      (node (ref "C8") (pin "2") (pinfunction "2_2") (pintype "passive"))
      (node (ref "L1") (pin "2") (pinfunction "2_2") (pintype "passive"))
      (node (ref "MOD1") (pin "5") (pinfunction "5_5") (pintype "bidirectional"))
    )
    (net (code "49") (name "Net-(C9-Pad1)") (class "Default")
      (node (ref "C9") (pin "1") (pinfunction "1_1") (pintype "passive"))
      (node (ref "IC11") (pin "0V") (pinfunction "0V_0V") (pintype "bidirectional"))
      (node (ref "MOD3") (pin "6") (pinfunction "6_6") (pintype "bidirectional"))
    )
    (net (code "50") (name "Net-(C9-Pad2)") (class "Default")
      (node (ref "C9") (pin "2") (pinfunction "2_2") (pintype "passive"))
      (node (ref "L3") (pin "2") (pinfunction "2_2") (pintype "passive"))
      (node (ref "MOD3") (pin "5") (pinfunction "5_5") (pintype "bidirectional"))
    )
    (net (code "51") (name "Net-(C10-Pad1)") (class "Default")
      (node (ref "C10") (pin "1") (pinfunction "1_1") (pintype "passive"))
      (node (ref "IC10") (pin "0V") (pinfunction "0V_0V") (pintype "bidirectional"))
      (node (ref "MOD2") (pin "6") (pinfunction "6_6") (pintype "bidirectional"))
    )
    (net (code "52") (name "Net-(C10-Pad2)") (class "Default")
      (node (ref "C10") (pin "2") (pinfunction "2_2") (pintype "passive"))
      (node (ref "L2") (pin "2") (pinfunction "2_2") (pintype "passive"))
      (node (ref "MOD2") (pin "5") (pinfunction "5_5") (pintype "bidirectional"))
    )
    (net (code "53") (name "Net-(C14-PadANODE)") (class "Default")
      (node (ref "C14") (pin "ANODE") (pinfunction "ANODE_ANODE") (pintype "bidirectional"))
      (node (ref "D1") (pin "C") (pinfunction "C_C") (pintype "passive"))
      (node (ref "IC8") (pin "VBB") (pinfunction "VBB_VBB") (pintype "bidirectional"))
      (node (ref "J1") (pin "PWR") (pinfunction "PWR_PWR") (pintype "bidirectional"))
    )
    (net (code "54") (name "Net-(F1-Pad1)") (class "Default")
      (node (ref "F1") (pin "1") (pinfunction "1_1") (pintype "bidirectional"))
      (node (ref "U$1") (pin "VIN") (pinfunction "VIN_VIN") (pintype "power_in"))
    )
    (net (code "55") (name "Net-(IC1-A)") (class "Default")
      (node (ref "IC1") (pin "8") (pinfunction "A_8") (pintype "bidirectional"))
      (node (ref "MOD1") (pin "4") (pinfunction "4_4") (pintype "bidirectional"))
      (node (ref "R13") (pin "1") (pinfunction "1_1") (pintype "passive"))
    )
    (net (code "56") (name "Net-(IC1-B)") (class "Default")
      (node (ref "IC1") (pin "7") (pinfunction "B_7") (pintype "bidirectional"))
      (node (ref "MOD1") (pin "3") (pinfunction "3_3") (pintype "bidirectional"))
      (node (ref "R13") (pin "2") (pinfunction "2_2") (pintype "passive"))
    )
    (net (code "57") (name "Net-(IC1-D)") (class "Default")
      (node (ref "IC1") (pin "3") (pinfunction "D_3") (pintype "bidirectional"))
      (node (ref "U$1") (pin "1") (pinfunction "1/TX1/MISO1/T_1") (pintype "bidirectional"))
    )
    (net (code "58") (name "Net-(IC1-R)") (class "Default")
      (node (ref "IC1") (pin "2") (pinfunction "R_2") (pintype "bidirectional"))
      (node (ref "U$1") (pin "0") (pinfunction "0/RX1/MOSI1/T_0") (pintype "bidirectional"))
    )
    (net (code "59") (name "Net-(IC1-Y)") (class "Default")
      (node (ref "IC1") (pin "5") (pinfunction "Y_5") (pintype "bidirectional"))
      (node (ref "MOD1") (pin "1") (pinfunction "1_1") (pintype "bidirectional"))
    )
    (net (code "60") (name "Net-(IC1-Z)") (class "Default")
      (node (ref "IC1") (pin "6") (pinfunction "Z_6") (pintype "bidirectional"))
      (node (ref "MOD1") (pin "2") (pinfunction "2_2") (pintype "bidirectional"))
    )
    (net (code "61") (name "Net-(IC2-A)") (class "Default")
      (node (ref "IC2") (pin "8") (pinfunction "A_8") (pintype "bidirectional"))
      (node (ref "MOD2") (pin "4") (pinfunction "4_4") (pintype "bidirectional"))
      (node (ref "R15") (pin "2") (pinfunction "2_2") (pintype "passive"))
    )
    (net (code "62") (name "Net-(IC2-B)") (class "Default")
      (node (ref "IC2") (pin "7") (pinfunction "B_7") (pintype "bidirectional"))
      (node (ref "MOD2") (pin "3") (pinfunction "3_3") (pintype "bidirectional"))
      (node (ref "R15") (pin "1") (pinfunction "1_1") (pintype "passive"))
    )
    (net (code "63") (name "Net-(IC2-D)") (class "Default")
      (node (ref "IC2") (pin "3") (pinfunction "D_3") (pintype "bidirectional"))
      (node (ref "U$1") (pin "8") (pinfunction "8/TX3/PWM_8") (pintype "bidirectional"))
    )
    (net (code "64") (name "Net-(IC2-R)") (class "Default")
      (node (ref "IC2") (pin "2") (pinfunction "R_2") (pintype "bidirectional"))
      (node (ref "U$1") (pin "7") (pinfunction "7/RX3/PWM_7") (pintype "bidirectional"))
    )
    (net (code "65") (name "Net-(IC2-Y)") (class "Default")
      (node (ref "IC2") (pin "5") (pinfunction "Y_5") (pintype "bidirectional"))
      (node (ref "MOD2") (pin "1") (pinfunction "1_1") (pintype "bidirectional"))
    )
    (net (code "66") (name "Net-(IC2-Z)") (class "Default")
      (node (ref "IC2") (pin "6") (pinfunction "Z_6") (pintype "bidirectional"))
      (node (ref "MOD2") (pin "2") (pinfunction "2_2") (pintype "bidirectional"))
    )
    (net (code "67") (name "Net-(IC3-A)") (class "Default")
      (node (ref "IC3") (pin "8") (pinfunction "A_8") (pintype "bidirectional"))
      (node (ref "MOD3") (pin "4") (pinfunction "4_4") (pintype "bidirectional"))
      (node (ref "R14") (pin "1") (pinfunction "1_1") (pintype "passive"))
    )
    (net (code "68") (name "Net-(IC3-B)") (class "Default")
      (node (ref "IC3") (pin "7") (pinfunction "B_7") (pintype "bidirectional"))
      (node (ref "MOD3") (pin "3") (pinfunction "3_3") (pintype "bidirectional"))
      (node (ref "R14") (pin "2") (pinfunction "2_2") (pintype "passive"))
    )
    (net (code "69") (name "Net-(IC3-D)") (class "Default")
      (node (ref "IC3") (pin "3") (pinfunction "D_3") (pintype "bidirectional"))
      (node (ref "U$1") (pin "24") (pinfunction "24_24") (pintype "bidirectional"))
    )
    (net (code "70") (name "Net-(IC3-R)") (class "Default")
      (node (ref "IC3") (pin "2") (pinfunction "R_2") (pintype "bidirectional"))
      (node (ref "U$1") (pin "25") (pinfunction "25_25") (pintype "bidirectional"))
    )
    (net (code "71") (name "Net-(IC3-Y)") (class "Default")
      (node (ref "IC3") (pin "5") (pinfunction "Y_5") (pintype "bidirectional"))
      (node (ref "MOD3") (pin "1") (pinfunction "1_1") (pintype "bidirectional"))
    )
    (net (code "72") (name "Net-(IC3-Z)") (class "Default")
      (node (ref "IC3") (pin "6") (pinfunction "Z_6") (pintype "bidirectional"))
      (node (ref "MOD3") (pin "2") (pinfunction "2_2") (pintype "bidirectional"))
    )
    (net (code "73") (name "Net-(IC4-VISO)") (class "Default")
      (node (ref "C5") (pin "2") (pinfunction "2_2") (pintype "passive"))
      (node (ref "C6") (pin "2") (pinfunction "2_2") (pintype "passive"))
      (node (ref "IC4") (pin "11") (pinfunction "VSEL_11") (pintype "passive"))
      (node (ref "IC4") (pin "16") (pinfunction "VISO_16") (pintype "passive"))
    )
    (net (code "74") (name "Net-(IC4-VOA)") (class "Default")
      (node (ref "C27") (pin "2") (pinfunction "2_2") (pintype "passive"))
      (node (ref "IC4") (pin "14") (pinfunction "VOA_14") (pintype "passive"))
      (node (ref "J5") (pin "S") (pinfunction "OUT_S") (pintype "bidirectional"))
    )
    (net (code "75") (name "Net-(IC4-VOB)") (class "Default")
      (node (ref "C26") (pin "1") (pinfunction "1_1") (pintype "passive"))
      (node (ref "IC4") (pin "13") (pinfunction "VOB_13") (pintype "passive"))
      (node (ref "J4") (pin "S") (pinfunction "OUT_S") (pintype "bidirectional"))
    )
    (net (code "76") (name "Net-(IC5-VID)") (class "Default")
      (node (ref "IC5") (pin "12") (pinfunction "VID_12") (pintype "input"))
      (node (ref "R9") (pin "1") (pinfunction "1_1") (pintype "passive"))
    )
    (net (code "77") (name "Net-(IC5-VOA)") (class "Default")
      (node (ref "IC5") (pin "15") (pinfunction "VOA_15") (pintype "output"))
      (node (ref "R12") (pin "1") (pinfunction "1_1") (pintype "passive"))
    )
    (net (code "78") (name "Net-(IC5-VOB)") (class "Default")
      (node (ref "IC5") (pin "14") (pinfunction "VOB_14") (pintype "output"))
      (node (ref "R11") (pin "1") (pinfunction "1_1") (pintype "passive"))
    )
    (net (code "79") (name "Net-(IC5-VOC)") (class "Default")
      (node (ref "IC5") (pin "13") (pinfunction "VOC_13") (pintype "output"))
      (node (ref "R10") (pin "1") (pinfunction "1_1") (pintype "passive"))
    )
    (net (code "80") (name "Net-(IC6-A1)") (class "Default")
      (node (ref "IC6") (pin "1") (pinfunction "A1_1") (pintype "bidirectional"))
      (node (ref "R2") (pin "1") (pinfunction "1_1") (pintype "passive"))
    )
    (net (code "81") (name "Net-(IC6-A2)") (class "Default")
      (node (ref "IC6") (pin "3") (pinfunction "A2_3") (pintype "bidirectional"))
      (node (ref "J3") (pin "GND") (pinfunction "GND_GND") (pintype "bidirectional"))
    )
    (net (code "82") (name "Net-(IC6-C1)") (class "Default")
      (node (ref "IC6") (pin "2") (pinfunction "C1_2") (pintype "bidirectional"))
      (node (ref "J2") (pin "GND") (pinfunction "GND_GND") (pintype "bidirectional"))
    )
    (net (code "83") (name "Net-(IC6-C2)") (class "Default")
      (node (ref "IC6") (pin "4") (pinfunction "C2_4") (pintype "bidirectional"))
      (node (ref "R3") (pin "1") (pinfunction "1_1") (pintype "passive"))
    )
    (net (code "84") (name "Net-(IC7-I{slash}O0)") (class "Default")
      (node (ref "IC7") (pin "4") (pinfunction "I/O0_4") (pintype "passive"))
      (node (ref "J6") (pin "P$1") (pinfunction "P$1_P$1") (pintype "bidirectional"))
    )
    (net (code "85") (name "Net-(IC7-I{slash}O1)") (class "Default")
      (node (ref "IC7") (pin "5") (pinfunction "I/O1_5") (pintype "passive"))
      (node (ref "J6") (pin "P$3") (pinfunction "P$3_P$3") (pintype "bidirectional"))
    )
    (net (code "86") (name "Net-(IC7-I{slash}O2)") (class "Default")
      (node (ref "IC7") (pin "6") (pinfunction "I/O2_6") (pintype "passive"))
      (node (ref "J6") (pin "P$5") (pinfunction "P$5_P$5") (pintype "bidirectional"))
    )
    (net (code "87") (name "Net-(IC7-I{slash}O3)") (class "Default")
      (node (ref "IC7") (pin "7") (pinfunction "I/O3_7") (pintype "passive"))
      (node (ref "J6") (pin "P$7") (pinfunction "P$7_P$7") (pintype "bidirectional"))
    )
    (net (code "88") (name "Net-(IC9-Pad+VOUT)") (class "Default")
      (node (ref "IC9") (pin "+VOUT") (pinfunction "+VOUT_+VOUT") (pintype "bidirectional"))
      (node (ref "L1") (pin "1") (pinfunction "1_1") (pintype "passive"))
    )
    (net (code "89") (name "Net-(IC10-Pad+VOUT)") (class "Default")
      (node (ref "IC10") (pin "+VOUT") (pinfunction "+VOUT_+VOUT") (pintype "bidirectional"))
      (node (ref "L2") (pin "1") (pinfunction "1_1") (pintype "passive"))
    )
    (net (code "90") (name "Net-(IC11-Pad+VOUT)") (class "Default")
      (node (ref "IC11") (pin "+VOUT") (pinfunction "+VOUT_+VOUT") (pintype "bidirectional"))
      (node (ref "L3") (pin "1") (pinfunction "1_1") (pintype "passive"))
    )
    (net (code "91") (name "Net-(IC12-2IN)") (class "Default")
      (node (ref "IC12") (pin "5") (pinfunction "2IN_5") (pintype "bidirectional"))
      (node (ref "PORT1") (pin "1") (pinfunction "1_1") (pintype "bidirectional"))
      (node (ref "R4") (pin "1") (pinfunction "1_1") (pintype "passive"))
    )
    (net (code "92") (name "Net-(IC12-3IN)") (class "Default")
      (node (ref "IC12") (pin "7") (pinfunction "3IN_7") (pintype "bidirectional"))
      (node (ref "PORT2") (pin "1") (pinfunction "1_1") (pintype "bidirectional"))
      (node (ref "R5") (pin "1") (pinfunction "1_1") (pintype "passive"))
    )
    (net (code "93") (name "Net-(IC12-4IN)") (class "Default")
      (node (ref "IC12") (pin "9") (pinfunction "4IN_9") (pintype "bidirectional"))
      (node (ref "PORT3") (pin "1") (pinfunction "1_1") (pintype "bidirectional"))
      (node (ref "R6") (pin "2") (pinfunction "2_2") (pintype "passive"))
    )
    (net (code "94") (name "Net-(IC12-5IN)") (class "Default")
      (node (ref "IC12") (pin "11") (pinfunction "5IN_11") (pintype "bidirectional"))
      (node (ref "PORT4") (pin "1") (pinfunction "1_1") (pintype "bidirectional"))
      (node (ref "R7") (pin "2") (pinfunction "2_2") (pintype "passive"))
    )
    (net (code "95") (name "Net-(IC12-6IN)") (class "Default")
      (node (ref "IC12") (pin "14") (pinfunction "6IN_14") (pintype "bidirectional"))
      (node (ref "PORT5") (pin "1") (pinfunction "1_1") (pintype "bidirectional"))
      (node (ref "R8") (pin "2") (pinfunction "2_2") (pintype "passive"))
    )
    (net (code "96") (name "Net-(IC14-Pad+VOUT)") (class "Default")
      (node (ref "IC14") (pin "+VOUT") (pinfunction "+VOUT_+VOUT") (pintype "bidirectional"))
      (node (ref "L4") (pin "1") (pinfunction "1_1") (pintype "passive"))
    )
    (net (code "97") (name "Net-(J2-OUT)") (class "Default")
      (node (ref "J2") (pin "S") (pinfunction "OUT_S") (pintype "bidirectional"))
      (node (ref "R2") (pin "2") (pinfunction "2_2") (pintype "passive"))
    )
    (net (code "98") (name "Net-(J3-OUT)") (class "Default")
      (node (ref "J3") (pin "S") (pinfunction "OUT_S") (pintype "bidirectional"))
      (node (ref "R3") (pin "2") (pinfunction "2_2") (pintype "passive"))
    )
    (net (code "99") (name "Net-(U$8-2)") (class "Default")
      (node (ref "R1") (pin "2") (pinfunction "2_2") (pintype "passive"))
      (node (ref "U$8") (pin "P$2") (pinfunction "2_P$2") (pintype "bidirectional"))
    )
    (net (code "100") (name "VCC") (class "Default")
      (node (ref "C1") (pin "1") (pinfunction "1_1") (pintype "passive"))
      (node (ref "C11") (pin "1") (pinfunction "1_1") (pintype "passive"))
      (node (ref "C12") (pin "2") (pinfunction "2_2") (pintype "passive"))
      (node (ref "C13") (pin "1") (pinfunction "1_1") (pintype "passive"))
      (node (ref "C16") (pin "1") (pinfunction "1_1") (pintype "passive"))
      (node (ref "C2") (pin "1") (pinfunction "1_1") (pintype "passive"))
      (node (ref "C3") (pin "1") (pinfunction "1_1") (pintype "passive"))
      (node (ref "IC1") (pin "1") (pinfunction "VCC_1") (pintype "bidirectional"))
      (node (ref "IC12") (pin "1") (pinfunction "VCC_1") (pintype "bidirectional"))
      (node (ref "IC2") (pin "1") (pinfunction "VCC_1") (pintype "bidirectional"))
      (node (ref "IC3") (pin "1") (pinfunction "VCC_1") (pintype "bidirectional"))
      (node (ref "IC5") (pin "1") (pinfunction "VDD1_1") (pintype "power_in"))
      (node (ref "IC6") (pin "8") (pinfunction "CL1_8") (pintype "bidirectional"))
      (node (ref "IC8") (pin "P$2") (pinfunction "P$2_P$2") (pintype "bidirectional"))
      (node (ref "IC8") (pin "P$3") (pinfunction "P$3_P$3") (pintype "bidirectional"))
      (node (ref "U$1") (pin "3.3V") (pinfunction "3.3V_3.3V") (pintype "power_in"))
      (node (ref "U$1") (pin "3.3V3") (pinfunction "3.3V_3.3V3") (pintype "power_in"))
    )
    (net (code "101") (name "unconnected-(IC4-NC-Pad12)") (class "Default")
      (node (ref "IC4") (pin "12") (pinfunction "NC_12") (pintype "passive"))
    )
    (net (code "102") (name "unconnected-(IC4-NC_2-Pad7)") (class "Default")
      (node (ref "IC4") (pin "7") (pinfunction "NC_2_7") (pintype "passive"))
    )
    (net (code "103") (name "unconnected-(IC4-RCSEL-Pad6)") (class "Default")
      (node (ref "IC4") (pin "6") (pinfunction "RCSEL_6") (pintype "passive"))
    )
    (net (code "104") (name "unconnected-(IC4-VE2-Pad10)") (class "Default")
      (node (ref "IC4") (pin "10") (pinfunction "VE2_10") (pintype "passive"))
    )
    (net (code "105") (name "unconnected-(IC5-NIC-Pad10)") (class "Default")
      (node (ref "IC5") (pin "10") (pinfunction "NIC_10") (pintype "no_connect"))
    )
    (net (code "106") (name "unconnected-(IC5-NIC_2-Pad7)") (class "Default")
      (node (ref "IC5") (pin "7") (pinfunction "NIC_2_7") (pintype "no_connect"))
    )
    (net (code "107") (name "unconnected-(IC7-I{slash}O4-Pad10)") (class "Default")
      (node (ref "IC7") (pin "10") (pinfunction "I/O4_10") (pintype "passive"))
    )
    (net (code "108") (name "unconnected-(IC7-I{slash}O5-Pad11)") (class "Default")
      (node (ref "IC7") (pin "11") (pinfunction "I/O5_11") (pintype "passive"))
    )
    (net (code "109") (name "unconnected-(IC7-I{slash}O6-Pad12)") (class "Default")
      (node (ref "IC7") (pin "12") (pinfunction "I/O6_12") (pintype "passive"))
    )
    (net (code "110") (name "unconnected-(IC8-PadP$1)") (class "Default")
      (node (ref "IC8") (pin "P$1") (pinfunction "P$1_P$1") (pintype "bidirectional"))
    )
    (net (code "111") (name "unconnected-(IC8-PadP$7)") (class "Default")
      (node (ref "IC8") (pin "P$7") (pinfunction "P$7_P$7") (pintype "bidirectional"))
    )
    (net (code "112") (name "unconnected-(IC8-PadP$9)") (class "Default")
      (node (ref "IC8") (pin "P$9") (pinfunction "P$9_P$9") (pintype "bidirectional"))
    )
    (net (code "113") (name "unconnected-(IC8-PadP$11)") (class "Default")
      (node (ref "IC8") (pin "P$11") (pinfunction "P$11_P$11") (pintype "bidirectional"))
    )
    (net (code "114") (name "unconnected-(IC8-PadP$14)") (class "Default")
      (node (ref "IC8") (pin "P$14") (pinfunction "P$14_P$14") (pintype "bidirectional"))
    )
    (net (code "115") (name "unconnected-(IC8-PadP$16)") (class "Default")
      (node (ref "IC8") (pin "P$16") (pinfunction "P$16_P$16") (pintype "bidirectional"))
    )
    (net (code "116") (name "unconnected-(IC8-PadP$17)") (class "Default")
      (node (ref "IC8") (pin "P$17") (pinfunction "P$17_P$17") (pintype "bidirectional"))
    )
    (net (code "117") (name "unconnected-(IC8-PadP$18)") (class "Default")
      (node (ref "IC8") (pin "P$18") (pinfunction "P$18_P$18") (pintype "bidirectional"))
    )
    (net (code "118") (name "unconnected-(IC8-PadP$20)") (class "Default")
      (node (ref "IC8") (pin "P$20") (pinfunction "P$20_P$20") (pintype "bidirectional"))
    )
    (net (code "119") (name "unconnected-(IC8-PadP$25)") (class "Default")
      (node (ref "IC8") (pin "P$25") (pinfunction "P$25_P$25") (pintype "bidirectional"))
    )
    (net (code "120") (name "unconnected-(IC8-PadP$26)") (class "Default")
      (node (ref "IC8") (pin "P$26") (pinfunction "P$26_P$26") (pintype "bidirectional"))
    )
    (net (code "121") (name "unconnected-(IC8-PadP$29)") (class "Default")
      (node (ref "IC8") (pin "P$29") (pinfunction "P$29_P$29") (pintype "bidirectional"))
    )
    (net (code "122") (name "unconnected-(IC8-PadP$30)") (class "Default")
      (node (ref "IC8") (pin "P$30") (pinfunction "P$30_P$30") (pintype "bidirectional"))
    )
    (net (code "123") (name "unconnected-(IC8-PadP$33)") (class "Default")
      (node (ref "IC8") (pin "P$33") (pinfunction "P$33_P$33") (pintype "bidirectional"))
    )
    (net (code "124") (name "unconnected-(IC8-PadP$34)") (class "Default")
      (node (ref "IC8") (pin "P$34") (pinfunction "P$34_P$34") (pintype "bidirectional"))
    )
    (net (code "125") (name "unconnected-(IC9-PadNC)") (class "Default")
      (node (ref "IC9") (pin "NC") (pinfunction "NC_NC") (pintype "bidirectional"))
    )
    (net (code "126") (name "unconnected-(IC10-PadNC)") (class "Default")
      (node (ref "IC10") (pin "NC") (pinfunction "NC_NC") (pintype "bidirectional"))
    )
    (net (code "127") (name "unconnected-(IC11-PadNC)") (class "Default")
      (node (ref "IC11") (pin "NC") (pinfunction "NC_NC") (pintype "bidirectional"))
    )
    (net (code "128") (name "unconnected-(IC12-1IN-Pad3)") (class "Default")
      (node (ref "IC12") (pin "3") (pinfunction "1IN_3") (pintype "bidirectional"))
    )
    (net (code "129") (name "unconnected-(IC12-1OUT-Pad2)") (class "Default")
      (node (ref "IC12") (pin "2") (pinfunction "1OUT_2") (pintype "bidirectional"))
    )
    (net (code "130") (name "unconnected-(IC12-NC-Pad16)") (class "Default")
      (node (ref "IC12") (pin "16") (pinfunction "NC_16") (pintype "bidirectional"))
    )
    (net (code "131") (name "unconnected-(IC12-NC2-Pad13)") (class "Default")
      (node (ref "IC12") (pin "13") (pinfunction "NC2_13") (pintype "bidirectional"))
    )
    (net (code "132") (name "unconnected-(IC13-COMP-Pad7)") (class "Default")
      (node (ref "IC13") (pin "7") (pinfunction "COMP_7") (pintype "passive"))
    )
    (net (code "133") (name "unconnected-(IC13-NIC-Pad3)") (class "Default")
      (node (ref "IC13") (pin "3") (pinfunction "NIC_3") (pintype "no_connect"))
    )
    (net (code "134") (name "unconnected-(IC13-TP-Pad8)") (class "Default")
      (node (ref "IC13") (pin "8") (pinfunction "TP_8") (pintype "passive"))
    )
    (net (code "135") (name "unconnected-(IC13-TP_2-Pad1)") (class "Default")
      (node (ref "IC13") (pin "1") (pinfunction "TP_2_1") (pintype "passive"))
    )
    (net (code "136") (name "unconnected-(IC13-TRIM-Pad5)") (class "Default")
      (node (ref "IC13") (pin "5") (pinfunction "TRIM_5") (pintype "passive"))
    )
    (net (code "137") (name "unconnected-(IC14-PadNC)") (class "Default")
      (node (ref "IC14") (pin "NC") (pinfunction "NC_NC") (pintype "bidirectional"))
    )
    (net (code "138") (name "unconnected-(MOD1-Pad7)") (class "Default")
      (node (ref "MOD1") (pin "7") (pinfunction "7_7") (pintype "bidirectional"))
    )
    (net (code "139") (name "unconnected-(MOD1-Pad8)") (class "Default")
      (node (ref "MOD1") (pin "8") (pinfunction "8_8") (pintype "bidirectional"))
    )
    (net (code "140") (name "unconnected-(MOD2-Pad7)") (class "Default")
      (node (ref "MOD2") (pin "7") (pinfunction "7_7") (pintype "bidirectional"))
    )
    (net (code "141") (name "unconnected-(MOD2-Pad8)") (class "Default")
      (node (ref "MOD2") (pin "8") (pinfunction "8_8") (pintype "bidirectional"))
    )
    (net (code "142") (name "unconnected-(MOD3-Pad7)") (class "Default")
      (node (ref "MOD3") (pin "7") (pinfunction "7_7") (pintype "bidirectional"))
    )
    (net (code "143") (name "unconnected-(MOD3-Pad8)") (class "Default")
      (node (ref "MOD3") (pin "8") (pinfunction "8_8") (pintype "bidirectional"))
    )
    (net (code "144") (name "unconnected-(PORT1-Pad2)") (class "Default")
      (node (ref "PORT1") (pin "2") (pinfunction "2_2") (pintype "bidirectional"))
    )
    (net (code "145") (name "unconnected-(PORT1-Pad8)") (class "Default")
      (node (ref "PORT1") (pin "8") (pinfunction "8_8") (pintype "bidirectional"))
    )
    (net (code "146") (name "unconnected-(PORT2-Pad2)") (class "Default")
      (node (ref "PORT2") (pin "2") (pinfunction "2_2") (pintype "bidirectional"))
    )
    (net (code "147") (name "unconnected-(PORT2-Pad8)") (class "Default")
      (node (ref "PORT2") (pin "8") (pinfunction "8_8") (pintype "bidirectional"))
    )
    (net (code "148") (name "unconnected-(PORT3-Pad2)") (class "Default")
      (node (ref "PORT3") (pin "2") (pinfunction "2_2") (pintype "bidirectional"))
    )
    (net (code "149") (name "unconnected-(PORT3-Pad8)") (class "Default")
      (node (ref "PORT3") (pin "8") (pinfunction "8_8") (pintype "bidirectional"))
    )
    (net (code "150") (name "unconnected-(PORT4-Pad2)") (class "Default")
      (node (ref "PORT4") (pin "2") (pinfunction "2_2") (pintype "bidirectional"))
    )
    (net (code "151") (name "unconnected-(PORT4-Pad8)") (class "Default")
      (node (ref "PORT4") (pin "8") (pinfunction "8_8") (pintype "bidirectional"))
    )
    (net (code "152") (name "unconnected-(PORT5-Pad2)") (class "Default")
      (node (ref "PORT5") (pin "2") (pinfunction "2_2") (pintype "bidirectional"))
    )
    (net (code "153") (name "unconnected-(PORT5-Pad8)") (class "Default")
      (node (ref "PORT5") (pin "8") (pinfunction "8_8") (pintype "bidirectional"))
    )
    (net (code "154") (name "unconnected-(U$1-10{slash}TX2{slash}PWM-Pad10)") (class "Default")
      (node (ref "U$1") (pin "10") (pinfunction "10/TX2/PWM_10") (pintype "bidirectional"))
    )
    (net (code "155") (name "unconnected-(U$1-29{slash}T{slash}PWM-Pad29)") (class "Default")
      (node (ref "U$1") (pin "29") (pinfunction "29/T/PWM_29") (pintype "bidirectional"))
    )
    (net (code "156") (name "unconnected-(U$1-30{slash}T{slash}PWM-Pad30)") (class "Default")
      (node (ref "U$1") (pin "30") (pinfunction "30/T/PWM_30") (pintype "bidirectional"))
    )
    (net (code "157") (name "unconnected-(U$1-31{slash}A12{slash}RX4-Pad31{slash}A12)") (class "Default")
      (node (ref "U$1") (pin "31/A12") (pinfunction "31/A12/RX4_31/A12") (pintype "bidirectional"))
    )
    (net (code "158") (name "unconnected-(U$1-34{slash}A15{slash}RX5{slash}CAN1-RX-Pad34{slash}A15)") (class "Default")
      (node (ref "U$1") (pin "34/A15") (pinfunction "34/A15/RX5/CAN1-RX_34/A15") (pintype "bidirectional"))
    )
    (net (code "159") (name "unconnected-(U$1-A21{slash}DAC0-PadA21)") (class "Default")
      (node (ref "U$1") (pin "A21") (pinfunction "A21/DAC0_A21") (pintype "bidirectional"))
    )
    (net (code "160") (name "unconnected-(U$1-Pad26)") (class "Default")
      (node (ref "U$1") (pin "26") (pinfunction "26_26") (pintype "bidirectional"))
    )
    (net (code "161") (name "unconnected-(U$1-Pad27)") (class "Default")
      (node (ref "U$1") (pin "27") (pinfunction "27_27") (pintype "bidirectional"))
    )
  )
)
